# ARD.net
KiCad netlist of a schematic drawn in Altium Designer
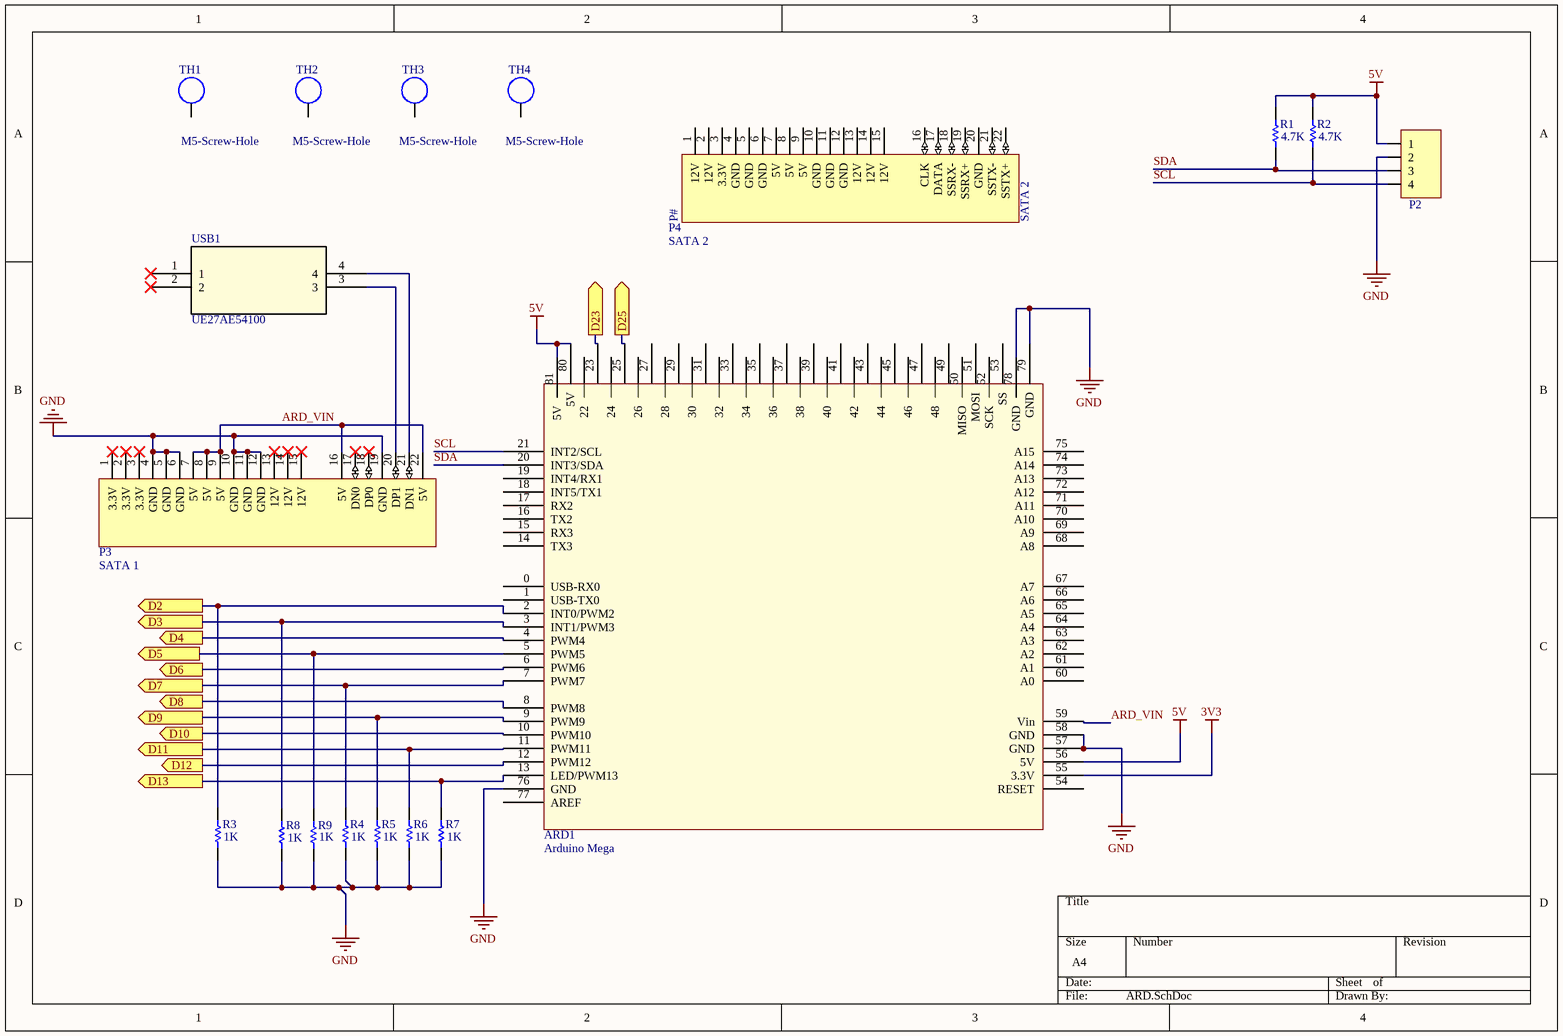
[diagram p0: ARD.SchDoc]

(export (version "E")
  (design (tool "Eeschema 10.0.6"))
  (components
    (comp (ref "ARD1")
      (value "Arduino Mega")
      (footprint "Arduino Mega")
      (libsource (lib "RSX_Modules") (part "Arduino Mega"))
    )
    (comp (ref "P2")
      (value "Mini-Fit Jr 4 Pos")
      (footprint "MOLEX 0039281043")
      (libsource (lib "RSX_Connectors") (part "Molex 0039281043"))
    )
    (comp (ref "P3")
      (value "SATA 1")
      (footprint "Amphenol 10101788-002CLF")
      (description "SATA connector. \r\nConnector 1 for option 1 as per Spec")
      (libsource (lib "RSX_Miscellaneous") (part "SATA 1"))
    )
    (comp (ref "P4")
      (value "SATA 2")
      (footprint "Amphenol 10101788-002CLF")
      (description "SATA connector. \r\nConnector 2 for option 1 as per Spec")
      (libsource (lib "RSX_Miscellaneous") (part "SATA 2"))
    )
    (comp (ref "R1")
      (value "4.7K")
      (footprint "RESC1608X06N_0603")
      (description "Resistor")
      (fields (field (name "Comment") "Res1") (field (name "PUBLISHER") "Altium Limited"))
      (libsource (lib "RSX_Resistors") (part "Res1"))
    )
    (comp (ref "R2")
      (value "4.7K")
      (footprint "RESC1608X06N_0603")
      (description "Resistor")
      (fields (field (name "Comment") "Res1") (field (name "PUBLISHER") "Altium Limited"))
      (libsource (lib "RSX_Resistors") (part "Res1"))
    )
    (comp (ref "R3")
      (value "1K")
      (footprint "RESC1608X06N_0603")
      (description "Resistor")
      (fields (field (name "Comment") "Res1") (field (name "PUBLISHER") "Altium Limited"))
      (libsource (lib "RSX_Resistors") (part "Res1"))
    )
    (comp (ref "R4")
      (value "1K")
      (footprint "RESC1608X06N_0603")
      (description "Resistor")
      (fields (field (name "Comment") "Res1") (field (name "PUBLISHER") "Altium Limited"))
      (libsource (lib "RSX_Resistors") (part "Res1"))
    )
    (comp (ref "R5")
      (value "1K")
      (footprint "RESC1608X06N_0603")
      (description "Resistor")
      (fields (field (name "Comment") "Res1") (field (name "PUBLISHER") "Altium Limited"))
      (libsource (lib "RSX_Resistors") (part "Res1"))
    )
    (comp (ref "R6")
      (value "1K")
      (footprint "RESC1608X06N_0603")
      (description "Resistor")
      (fields (field (name "Comment") "Res1") (field (name "PUBLISHER") "Altium Limited"))
      (libsource (lib "RSX_Resistors") (part "Res1"))
    )
    (comp (ref "R7")
      (value "1K")
      (footprint "RESC1608X06N_0603")
      (description "Resistor")
      (fields (field (name "Comment") "Res1") (field (name "PUBLISHER") "Altium Limited"))
      (libsource (lib "RSX_Resistors") (part "Res1"))
    )
    (comp (ref "R8")
      (value "1K")
      (footprint "RESC1608X06N_0603")
      (description "Resistor")
      (fields (field (name "Comment") "Res1") (field (name "PUBLISHER") "Altium Limited"))
      (libsource (lib "RSX_Resistors") (part "Res1"))
    )
    (comp (ref "R9")
      (value "1K")
      (footprint "RESC1608X06N_0603")
      (description "Resistor")
      (fields (field (name "Comment") "Res1") (field (name "PUBLISHER") "Altium Limited"))
      (libsource (lib "RSX_Resistors") (part "Res1"))
    )
    (comp (ref "TH1")
      (value "M5-Screw-Hole")
      (footprint "M5_Screw_Hole")
      (libsource (lib "RSX_Mechanicals") (part "M5-Screw-Hole"))
    )
    (comp (ref "TH2")
      (value "M5-Screw-Hole")
      (footprint "M5_Screw_Hole")
      (libsource (lib "RSX_Mechanicals") (part "M5-Screw-Hole"))
    )
    (comp (ref "TH3")
      (value "M5-Screw-Hole")
      (footprint "M5_Screw_Hole")
      (libsource (lib "RSX_Mechanicals") (part "M5-Screw-Hole"))
    )
    (comp (ref "TH4")
      (value "M5-Screw-Hole")
      (footprint "M5_Screw_Hole")
      (libsource (lib "RSX_Mechanicals") (part "M5-Screw-Hole"))
    )
    (comp (ref "USB1")
      (value "UE27AE54100")
      (footprint "UE27AE54100_AMP")
      (description "No Description Available")
      (fields (field (name "COPYRIGHT") "Copyright (C) 2022 Ultra Librarian. All rights reserved."))
      (libsource (lib "UE27AE54100") (part "UE27AE54100"))
    )
  )
  (nets
    (net (code "1") (name "/ARD_VIN") (class "Default")
      (node (ref "ARD1") (pin "59") (pinfunction "Vin_59") (pintype "passive"))
      (node (ref "P3") (pin "16") (pinfunction "5V_16") (pintype "power_in"))
      (node (ref "P3") (pin "22") (pinfunction "5V_22") (pintype "power_in"))
      (node (ref "P3") (pin "7") (pinfunction "5V_7") (pintype "power_in"))
      (node (ref "P3") (pin "8") (pinfunction "5V_8") (pintype "power_in"))
      (node (ref "P3") (pin "9") (pinfunction "5V_9") (pintype "power_in"))
    )
    (net (code "2") (name "/D2") (class "Default")
      (node (ref "ARD1") (pin "2") (pinfunction "INT0/PWM2_2") (pintype "passive"))
      (node (ref "R3") (pin "2") (pinfunction "2_2") (pintype "passive"))
    )
    (net (code "3") (name "/D3") (class "Default")
      (node (ref "ARD1") (pin "3") (pinfunction "INT1/PWM3_3") (pintype "passive"))
      (node (ref "R8") (pin "2") (pinfunction "2_2") (pintype "passive"))
    )
    (net (code "4") (name "/D4") (class "Default")
      (node (ref "ARD1") (pin "4") (pinfunction "PWM4_4") (pintype "passive"))
    )
    (net (code "5") (name "/D5") (class "Default")
      (node (ref "ARD1") (pin "5") (pinfunction "PWM5_5") (pintype "passive"))
      (node (ref "R9") (pin "2") (pinfunction "2_2") (pintype "passive"))
    )
    (net (code "6") (name "/D6") (class "Default")
      (node (ref "ARD1") (pin "6") (pinfunction "PWM6_6") (pintype "passive"))
    )
    (net (code "7") (name "/D7") (class "Default")
      (node (ref "ARD1") (pin "7") (pinfunction "PWM7_7") (pintype "passive"))
      (node (ref "R4") (pin "2") (pinfunction "2_2") (pintype "passive"))
    )
    (net (code "8") (name "/D8") (class "Default")
      (node (ref "ARD1") (pin "8") (pinfunction "PWM8_8") (pintype "passive"))
    )
    (net (code "9") (name "/D9") (class "Default")
      (node (ref "ARD1") (pin "9") (pinfunction "PWM9_9") (pintype "passive"))
      (node (ref "R5") (pin "2") (pinfunction "2_2") (pintype "passive"))
    )
    (net (code "10") (name "/D10") (class "Default")
      (node (ref "ARD1") (pin "10") (pinfunction "PWM10_10") (pintype "passive"))
    )
    (net (code "11") (name "/D11") (class "Default")
      (node (ref "ARD1") (pin "11") (pinfunction "PWM11_11") (pintype "passive"))
      (node (ref "R6") (pin "2") (pinfunction "2_2") (pintype "passive"))
    )
    (net (code "12") (name "/D12") (class "Default")
      (node (ref "ARD1") (pin "12") (pinfunction "PWM12_12") (pintype "passive"))
    )
    (net (code "13") (name "/D13") (class "Default")
      (node (ref "ARD1") (pin "13") (pinfunction "LED/PWM13_13") (pintype "passive"))
      (node (ref "R7") (pin "2") (pinfunction "2_2") (pintype "passive"))
    )
    (net (code "14") (name "/D23") (class "Default")
      (node (ref "ARD1") (pin "23") (pinfunction "23_23") (pintype "passive"))
    )
    (net (code "15") (name "/D25") (class "Default")
      (node (ref "ARD1") (pin "25") (pinfunction "25_25") (pintype "passive"))
    )
    (net (code "16") (name "/SCL") (class "Default")
      (node (ref "ARD1") (pin "21") (pinfunction "INT2/SCL_21") (pintype "passive"))
      (node (ref "P2") (pin "4") (pinfunction "4_4") (pintype "passive"))
      (node (ref "R2") (pin "1") (pinfunction "1_1") (pintype "passive"))
    )
    (net (code "17") (name "/SDA") (class "Default")
      (node (ref "ARD1") (pin "20") (pinfunction "INT3/SDA_20") (pintype "passive"))
      (node (ref "P2") (pin "3") (pinfunction "3_3") (pintype "passive"))
      (node (ref "R1") (pin "1") (pinfunction "1_1") (pintype "passive"))
    )
    (net (code "18") (name "3V3") (class "Default")
      (node (ref "ARD1") (pin "55") (pinfunction "3.3V_55") (pintype "passive"))
    )
    (net (code "19") (name "5V") (class "Default")
      (node (ref "ARD1") (pin "56") (pinfunction "5V_56") (pintype "passive"))
      (node (ref "ARD1") (pin "80") (pinfunction "5V_80") (pintype "passive"))
      (node (ref "ARD1") (pin "81") (pinfunction "5V_81") (pintype "passive"))
      (node (ref "P2") (pin "1") (pinfunction "1_1") (pintype "passive"))
      (node (ref "R1") (pin "2") (pinfunction "2_2") (pintype "passive"))
      (node (ref "R2") (pin "2") (pinfunction "2_2") (pintype "passive"))
    )
    (net (code "20") (name "GND") (class "Default")
      (node (ref "ARD1") (pin "57") (pinfunction "GND_57") (pintype "passive"))
      (node (ref "ARD1") (pin "58") (pinfunction "GND_58") (pintype "passive"))
      (node (ref "ARD1") (pin "76") (pinfunction "GND_76") (pintype "passive"))
      (node (ref "ARD1") (pin "78") (pinfunction "GND_78") (pintype "passive"))
      (node (ref "ARD1") (pin "79") (pinfunction "GND_79") (pintype "passive"))
      (node (ref "P2") (pin "2") (pinfunction "2_2") (pintype "passive"))
      (node (ref "P3") (pin "10") (pinfunction "GND_10") (pintype "power_in"))
      (node (ref "P3") (pin "11") (pinfunction "GND_11") (pintype "power_in"))
      (node (ref "P3") (pin "12") (pinfunction "GND_12") (pintype "power_in"))
      (node (ref "P3") (pin "19") (pinfunction "GND_19") (pintype "power_in"))
      (node (ref "P3") (pin "4") (pinfunction "GND_4") (pintype "power_in"))
      (node (ref "P3") (pin "5") (pinfunction "GND_5") (pintype "power_in"))
      (node (ref "P3") (pin "6") (pinfunction "GND_6") (pintype "power_in"))
      (node (ref "R3") (pin "1") (pinfunction "1_1") (pintype "passive"))
      (node (ref "R4") (pin "1") (pinfunction "1_1") (pintype "passive"))
      (node (ref "R5") (pin "1") (pinfunction "1_1") (pintype "passive"))
      (node (ref "R6") (pin "1") (pinfunction "1_1") (pintype "passive"))
      (node (ref "R7") (pin "1") (pinfunction "1_1") (pintype "passive"))
      (node (ref "R8") (pin "1") (pinfunction "1_1") (pintype "passive"))
      (node (ref "R9") (pin "1") (pinfunction "1_1") (pintype "passive"))
    )
    (net (code "21") (name "Net-(P3-DN1)") (class "Default")
      (node (ref "P3") (pin "21") (pinfunction "DN1_21") (pintype "bidirectional"))
      (node (ref "USB1") (pin "4") (pinfunction "4_4") (pintype "passive"))
    )
    (net (code "22") (name "Net-(P3-DP1)") (class "Default")
      (node (ref "P3") (pin "20") (pinfunction "DP1_20") (pintype "bidirectional"))
      (node (ref "USB1") (pin "3") (pinfunction "3_3") (pintype "passive"))
    )
    (net (code "23") (name "unconnected-(ARD1-A0-Pad60)") (class "Default")
      (node (ref "ARD1") (pin "60") (pinfunction "A0_60") (pintype "passive"))
    )
    (net (code "24") (name "unconnected-(ARD1-A1-Pad61)") (class "Default")
      (node (ref "ARD1") (pin "61") (pinfunction "A1_61") (pintype "passive"))
    )
    (net (code "25") (name "unconnected-(ARD1-A2-Pad62)") (class "Default")
      (node (ref "ARD1") (pin "62") (pinfunction "A2_62") (pintype "passive"))
    )
    (net (code "26") (name "unconnected-(ARD1-A3-Pad63)") (class "Default")
      (node (ref "ARD1") (pin "63") (pinfunction "A3_63") (pintype "passive"))
    )
    (net (code "27") (name "unconnected-(ARD1-A4-Pad64)") (class "Default")
      (node (ref "ARD1") (pin "64") (pinfunction "A4_64") (pintype "passive"))
    )
    (net (code "28") (name "unconnected-(ARD1-A5-Pad65)") (class "Default")
      (node (ref "ARD1") (pin "65") (pinfunction "A5_65") (pintype "passive"))
    )
    (net (code "29") (name "unconnected-(ARD1-A6-Pad66)") (class "Default")
      (node (ref "ARD1") (pin "66") (pinfunction "A6_66") (pintype "passive"))
    )
    (net (code "30") (name "unconnected-(ARD1-A7-Pad67)") (class "Default")
      (node (ref "ARD1") (pin "67") (pinfunction "A7_67") (pintype "passive"))
    )
    (net (code "31") (name "unconnected-(ARD1-A8-Pad68)") (class "Default")
      (node (ref "ARD1") (pin "68") (pinfunction "A8_68") (pintype "passive"))
    )
    (net (code "32") (name "unconnected-(ARD1-A9-Pad69)") (class "Default")
      (node (ref "ARD1") (pin "69") (pinfunction "A9_69") (pintype "passive"))
    )
    (net (code "33") (name "unconnected-(ARD1-A10-Pad70)") (class "Default")
      (node (ref "ARD1") (pin "70") (pinfunction "A10_70") (pintype "passive"))
    )
    (net (code "34") (name "unconnected-(ARD1-A11-Pad71)") (class "Default")
      (node (ref "ARD1") (pin "71") (pinfunction "A11_71") (pintype "passive"))
    )
    (net (code "35") (name "unconnected-(ARD1-A12-Pad72)") (class "Default")
      (node (ref "ARD1") (pin "72") (pinfunction "A12_72") (pintype "passive"))
    )
    (net (code "36") (name "unconnected-(ARD1-A13-Pad73)") (class "Default")
      (node (ref "ARD1") (pin "73") (pinfunction "A13_73") (pintype "passive"))
    )
    (net (code "37") (name "unconnected-(ARD1-A14-Pad74)") (class "Default")
      (node (ref "ARD1") (pin "74") (pinfunction "A14_74") (pintype "passive"))
    )
    (net (code "38") (name "unconnected-(ARD1-A15-Pad75)") (class "Default")
      (node (ref "ARD1") (pin "75") (pinfunction "A15_75") (pintype "passive"))
    )
    (net (code "39") (name "unconnected-(ARD1-AREF-Pad77)") (class "Default")
      (node (ref "ARD1") (pin "77") (pinfunction "AREF_77") (pintype "passive"))
    )
    (net (code "40") (name "unconnected-(ARD1-INT4{slash}RX1-Pad19)") (class "Default")
      (node (ref "ARD1") (pin "19") (pinfunction "INT4/RX1_19") (pintype "passive"))
    )
    (net (code "41") (name "unconnected-(ARD1-INT5{slash}TX1-Pad18)") (class "Default")
      (node (ref "ARD1") (pin "18") (pinfunction "INT5/TX1_18") (pintype "passive"))
    )
    (net (code "42") (name "unconnected-(ARD1-MISO-Pad50)") (class "Default")
      (node (ref "ARD1") (pin "50") (pinfunction "MISO_50") (pintype "passive"))
    )
    (net (code "43") (name "unconnected-(ARD1-MOSI-Pad51)") (class "Default")
      (node (ref "ARD1") (pin "51") (pinfunction "MOSI_51") (pintype "passive"))
    )
    (net (code "44") (name "unconnected-(ARD1-Pad22)") (class "Default")
      (node (ref "ARD1") (pin "22") (pinfunction "22_22") (pintype "passive"))
    )
    (net (code "45") (name "unconnected-(ARD1-Pad24)") (class "Default")
      (node (ref "ARD1") (pin "24") (pinfunction "24_24") (pintype "passive"))
    )
    (net (code "46") (name "unconnected-(ARD1-Pad26)") (class "Default")
      (node (ref "ARD1") (pin "26") (pinfunction "26_26") (pintype "passive"))
    )
    (net (code "47") (name "unconnected-(ARD1-Pad27)") (class "Default")
      (node (ref "ARD1") (pin "27") (pinfunction "27_27") (pintype "passive"))
    )
    (net (code "48") (name "unconnected-(ARD1-Pad28)") (class "Default")
      (node (ref "ARD1") (pin "28") (pinfunction "28_28") (pintype "passive"))
    )
    (net (code "49") (name "unconnected-(ARD1-Pad29)") (class "Default")
      (node (ref "ARD1") (pin "29") (pinfunction "29_29") (pintype "passive"))
    )
    (net (code "50") (name "unconnected-(ARD1-Pad30)") (class "Default")
      (node (ref "ARD1") (pin "30") (pinfunction "30_30") (pintype "passive"))
    )
    (net (code "51") (name "unconnected-(ARD1-Pad31)") (class "Default")
      (node (ref "ARD1") (pin "31") (pinfunction "31_31") (pintype "passive"))
    )
    (net (code "52") (name "unconnected-(ARD1-Pad32)") (class "Default")
      (node (ref "ARD1") (pin "32") (pinfunction "32_32") (pintype "passive"))
    )
    (net (code "53") (name "unconnected-(ARD1-Pad33)") (class "Default")
      (node (ref "ARD1") (pin "33") (pinfunction "33_33") (pintype "passive"))
    )
    (net (code "54") (name "unconnected-(ARD1-Pad34)") (class "Default")
      (node (ref "ARD1") (pin "34") (pinfunction "34_34") (pintype "passive"))
    )
    (net (code "55") (name "unconnected-(ARD1-Pad35)") (class "Default")
      (node (ref "ARD1") (pin "35") (pinfunction "35_35") (pintype "passive"))
    )
    (net (code "56") (name "unconnected-(ARD1-Pad36)") (class "Default")
      (node (ref "ARD1") (pin "36") (pinfunction "36_36") (pintype "passive"))
    )
    (net (code "57") (name "unconnected-(ARD1-Pad37)") (class "Default")
      (node (ref "ARD1") (pin "37") (pinfunction "37_37") (pintype "passive"))
    )
    (net (code "58") (name "unconnected-(ARD1-Pad38)") (class "Default")
      (node (ref "ARD1") (pin "38") (pinfunction "38_38") (pintype "passive"))
    )
    (net (code "59") (name "unconnected-(ARD1-Pad39)") (class "Default")
      (node (ref "ARD1") (pin "39") (pinfunction "39_39") (pintype "passive"))
    )
    (net (code "60") (name "unconnected-(ARD1-Pad40)") (class "Default")
      (node (ref "ARD1") (pin "40") (pinfunction "40_40") (pintype "passive"))
    )
    (net (code "61") (name "unconnected-(ARD1-Pad41)") (class "Default")
      (node (ref "ARD1") (pin "41") (pinfunction "41_41") (pintype "passive"))
    )
    (net (code "62") (name "unconnected-(ARD1-Pad42)") (class "Default")
      (node (ref "ARD1") (pin "42") (pinfunction "42_42") (pintype "passive"))
    )
    (net (code "63") (name "unconnected-(ARD1-Pad43)") (class "Default")
      (node (ref "ARD1") (pin "43") (pinfunction "43_43") (pintype "passive"))
    )
    (net (code "64") (name "unconnected-(ARD1-Pad44)") (class "Default")
      (node (ref "ARD1") (pin "44") (pinfunction "44_44") (pintype "passive"))
    )
    (net (code "65") (name "unconnected-(ARD1-Pad45)") (class "Default")
      (node (ref "ARD1") (pin "45") (pinfunction "45_45") (pintype "passive"))
    )
    (net (code "66") (name "unconnected-(ARD1-Pad46)") (class "Default")
      (node (ref "ARD1") (pin "46") (pinfunction "46_46") (pintype "passive"))
    )
    (net (code "67") (name "unconnected-(ARD1-Pad47)") (class "Default")
      (node (ref "ARD1") (pin "47") (pinfunction "47_47") (pintype "passive"))
    )
    (net (code "68") (name "unconnected-(ARD1-Pad48)") (class "Default")
      (node (ref "ARD1") (pin "48") (pinfunction "48_48") (pintype "passive"))
    )
    (net (code "69") (name "unconnected-(ARD1-Pad49)") (class "Default")
      (node (ref "ARD1") (pin "49") (pinfunction "49_49") (pintype "passive"))
    )
    (net (code "70") (name "unconnected-(ARD1-RESET-Pad54)") (class "Default")
      (node (ref "ARD1") (pin "54") (pinfunction "RESET_54") (pintype "passive"))
    )
    (net (code "71") (name "unconnected-(ARD1-RX2-Pad17)") (class "Default")
      (node (ref "ARD1") (pin "17") (pinfunction "RX2_17") (pintype "passive"))
    )
    (net (code "72") (name "unconnected-(ARD1-RX3-Pad15)") (class "Default")
      (node (ref "ARD1") (pin "15") (pinfunction "RX3_15") (pintype "passive"))
    )
    (net (code "73") (name "unconnected-(ARD1-SCK-Pad52)") (class "Default")
      (node (ref "ARD1") (pin "52") (pinfunction "SCK_52") (pintype "passive"))
    )
    (net (code "74") (name "unconnected-(ARD1-SS-Pad53)") (class "Default")
      (node (ref "ARD1") (pin "53") (pinfunction "SS_53") (pintype "passive"))
    )
    (net (code "75") (name "unconnected-(ARD1-TX2-Pad16)") (class "Default")
      (node (ref "ARD1") (pin "16") (pinfunction "TX2_16") (pintype "passive"))
    )
    (net (code "76") (name "unconnected-(ARD1-TX3-Pad14)") (class "Default")
      (node (ref "ARD1") (pin "14") (pinfunction "TX3_14") (pintype "passive"))
    )
    (net (code "77") (name "unconnected-(ARD1-USB-RX0-Pad0)") (class "Default")
      (node (ref "ARD1") (pin "0") (pinfunction "USB-RX0_0") (pintype "passive"))
    )
    (net (code "78") (name "unconnected-(ARD1-USB-TX0-Pad1)") (class "Default")
      (node (ref "ARD1") (pin "1") (pinfunction "USB-TX0_1") (pintype "passive"))
    )
    (net (code "79") (name "unconnected-(P3-3.3V-Pad1)") (class "Default")
      (node (ref "P3") (pin "1") (pinfunction "3.3V_1") (pintype "power_in+no_connect"))
    )
    (net (code "80") (name "unconnected-(P3-3.3V-Pad2)") (class "Default")
      (node (ref "P3") (pin "2") (pinfunction "3.3V_2") (pintype "power_in+no_connect"))
    )
    (net (code "81") (name "unconnected-(P3-3.3V-Pad3)") (class "Default")
      (node (ref "P3") (pin "3") (pinfunction "3.3V_3") (pintype "power_in+no_connect"))
    )
    (net (code "82") (name "unconnected-(P3-12V-Pad13)") (class "Default")
      (node (ref "P3") (pin "13") (pinfunction "12V_13") (pintype "power_in+no_connect"))
    )
    (net (code "83") (name "unconnected-(P3-12V-Pad14)") (class "Default")
      (node (ref "P3") (pin "14") (pinfunction "12V_14") (pintype "power_in+no_connect"))
    )
    (net (code "84") (name "unconnected-(P3-12V-Pad15)") (class "Default")
      (node (ref "P3") (pin "15") (pinfunction "12V_15") (pintype "power_in+no_connect"))
    )
    (net (code "85") (name "unconnected-(P3-DN0-Pad17)") (class "Default")
      (node (ref "P3") (pin "17") (pinfunction "DN0_17") (pintype "bidirectional+no_connect"))
    )
    (net (code "86") (name "unconnected-(P3-DP0-Pad18)") (class "Default")
      (node (ref "P3") (pin "18") (pinfunction "DP0_18") (pintype "bidirectional+no_connect"))
    )
    (net (code "87") (name "unconnected-(P4-3.3V-Pad3)") (class "Default")
      (node (ref "P4") (pin "3") (pinfunction "3.3V_3") (pintype "power_in"))
    )
    (net (code "88") (name "unconnected-(P4-5V-Pad7)") (class "Default")
      (node (ref "P4") (pin "7") (pinfunction "5V_7") (pintype "power_in"))
    )
    (net (code "89") (name "unconnected-(P4-5V-Pad8)") (class "Default")
      (node (ref "P4") (pin "8") (pinfunction "5V_8") (pintype "power_in"))
    )
    (net (code "90") (name "unconnected-(P4-5V-Pad9)") (class "Default")
      (node (ref "P4") (pin "9") (pinfunction "5V_9") (pintype "power_in"))
    )
    (net (code "91") (name "unconnected-(P4-12V-Pad1)") (class "Default")
      (node (ref "P4") (pin "1") (pinfunction "12V_1") (pintype "power_in"))
    )
    (net (code "92") (name "unconnected-(P4-12V-Pad2)") (class "Default")
      (node (ref "P4") (pin "2") (pinfunction "12V_2") (pintype "power_in"))
    )
    (net (code "93") (name "unconnected-(P4-12V-Pad13)") (class "Default")
      (node (ref "P4") (pin "13") (pinfunction "12V_13") (pintype "power_in"))
    )
    (net (code "94") (name "unconnected-(P4-12V-Pad14)") (class "Default")
      (node (ref "P4") (pin "14") (pinfunction "12V_14") (pintype "power_in"))
    )
    (net (code "95") (name "unconnected-(P4-12V-Pad15)") (class "Default")
      (node (ref "P4") (pin "15") (pinfunction "12V_15") (pintype "power_in"))
    )
    (net (code "96") (name "unconnected-(P4-CLK-Pad16)") (class "Default")
      (node (ref "P4") (pin "16") (pinfunction "CLK_16") (pintype "bidirectional"))
    )
    (net (code "97") (name "unconnected-(P4-DATA-Pad17)") (class "Default")
      (node (ref "P4") (pin "17") (pinfunction "DATA_17") (pintype "bidirectional"))
    )
    (net (code "98") (name "unconnected-(P4-GND-Pad4)") (class "Default")
      (node (ref "P4") (pin "4") (pinfunction "GND_4") (pintype "power_in"))
    )
    (net (code "99") (name "unconnected-(P4-GND-Pad5)") (class "Default")
      (node (ref "P4") (pin "5") (pinfunction "GND_5") (pintype "power_in"))
    )
    (net (code "100") (name "unconnected-(P4-GND-Pad6)") (class "Default")
      (node (ref "P4") (pin "6") (pinfunction "GND_6") (pintype "power_in"))
    )
    (net (code "101") (name "unconnected-(P4-GND-Pad10)") (class "Default")
      (node (ref "P4") (pin "10") (pinfunction "GND_10") (pintype "power_in"))
    )
    (net (code "102") (name "unconnected-(P4-GND-Pad11)") (class "Default")
      (node (ref "P4") (pin "11") (pinfunction "GND_11") (pintype "power_in"))
    )
    (net (code "103") (name "unconnected-(P4-GND-Pad12)") (class "Default")
      (node (ref "P4") (pin "12") (pinfunction "GND_12") (pintype "power_in"))
    )
    (net (code "104") (name "unconnected-(P4-GND-Pad20)") (class "Default")
      (node (ref "P4") (pin "20") (pinfunction "GND_20") (pintype "power_in"))
    )
    (net (code "105") (name "unconnected-(P4-SSRX+-Pad19)") (class "Default")
      (node (ref "P4") (pin "19") (pinfunction "SSRX+_19") (pintype "bidirectional"))
    )
    (net (code "106") (name "unconnected-(P4-SSRX--Pad18)") (class "Default")
      (node (ref "P4") (pin "18") (pinfunction "SSRX-_18") (pintype "bidirectional"))
    )
    (net (code "107") (name "unconnected-(P4-SSTX+-Pad22)") (class "Default")
      (node (ref "P4") (pin "22") (pinfunction "SSTX+_22") (pintype "bidirectional"))
    )
    (net (code "108") (name "unconnected-(P4-SSTX--Pad21)") (class "Default")
      (node (ref "P4") (pin "21") (pinfunction "SSTX-_21") (pintype "bidirectional"))
    )
    (net (code "109") (name "unconnected-(TH1-Pad1)") (class "Default")
      (node (ref "TH1") (pin "1") (pinfunction "1_1") (pintype "passive"))
    )
    (net (code "110") (name "unconnected-(TH2-Pad1)") (class "Default")
      (node (ref "TH2") (pin "1") (pinfunction "1_1") (pintype "passive"))
    )
    (net (code "111") (name "unconnected-(TH3-Pad1)") (class "Default")
      (node (ref "TH3") (pin "1") (pinfunction "1_1") (pintype "passive"))
    )
    (net (code "112") (name "unconnected-(TH4-Pad1)") (class "Default")
      (node (ref "TH4") (pin "1") (pinfunction "1_1") (pintype "passive"))
    )
    (net (code "113") (name "unconnected-(USB1-Pad1)") (class "Default")
      (node (ref "USB1") (pin "1") (pinfunction "1_1") (pintype "passive+no_connect"))
    )
    (net (code "114") (name "unconnected-(USB1-Pad2)") (class "Default")
      (node (ref "USB1") (pin "2") (pinfunction "2_2") (pintype "passive+no_connect"))
    )
  )
)
